# bargraph.net
KiCad netlist of a schematic drawn in EAGLE
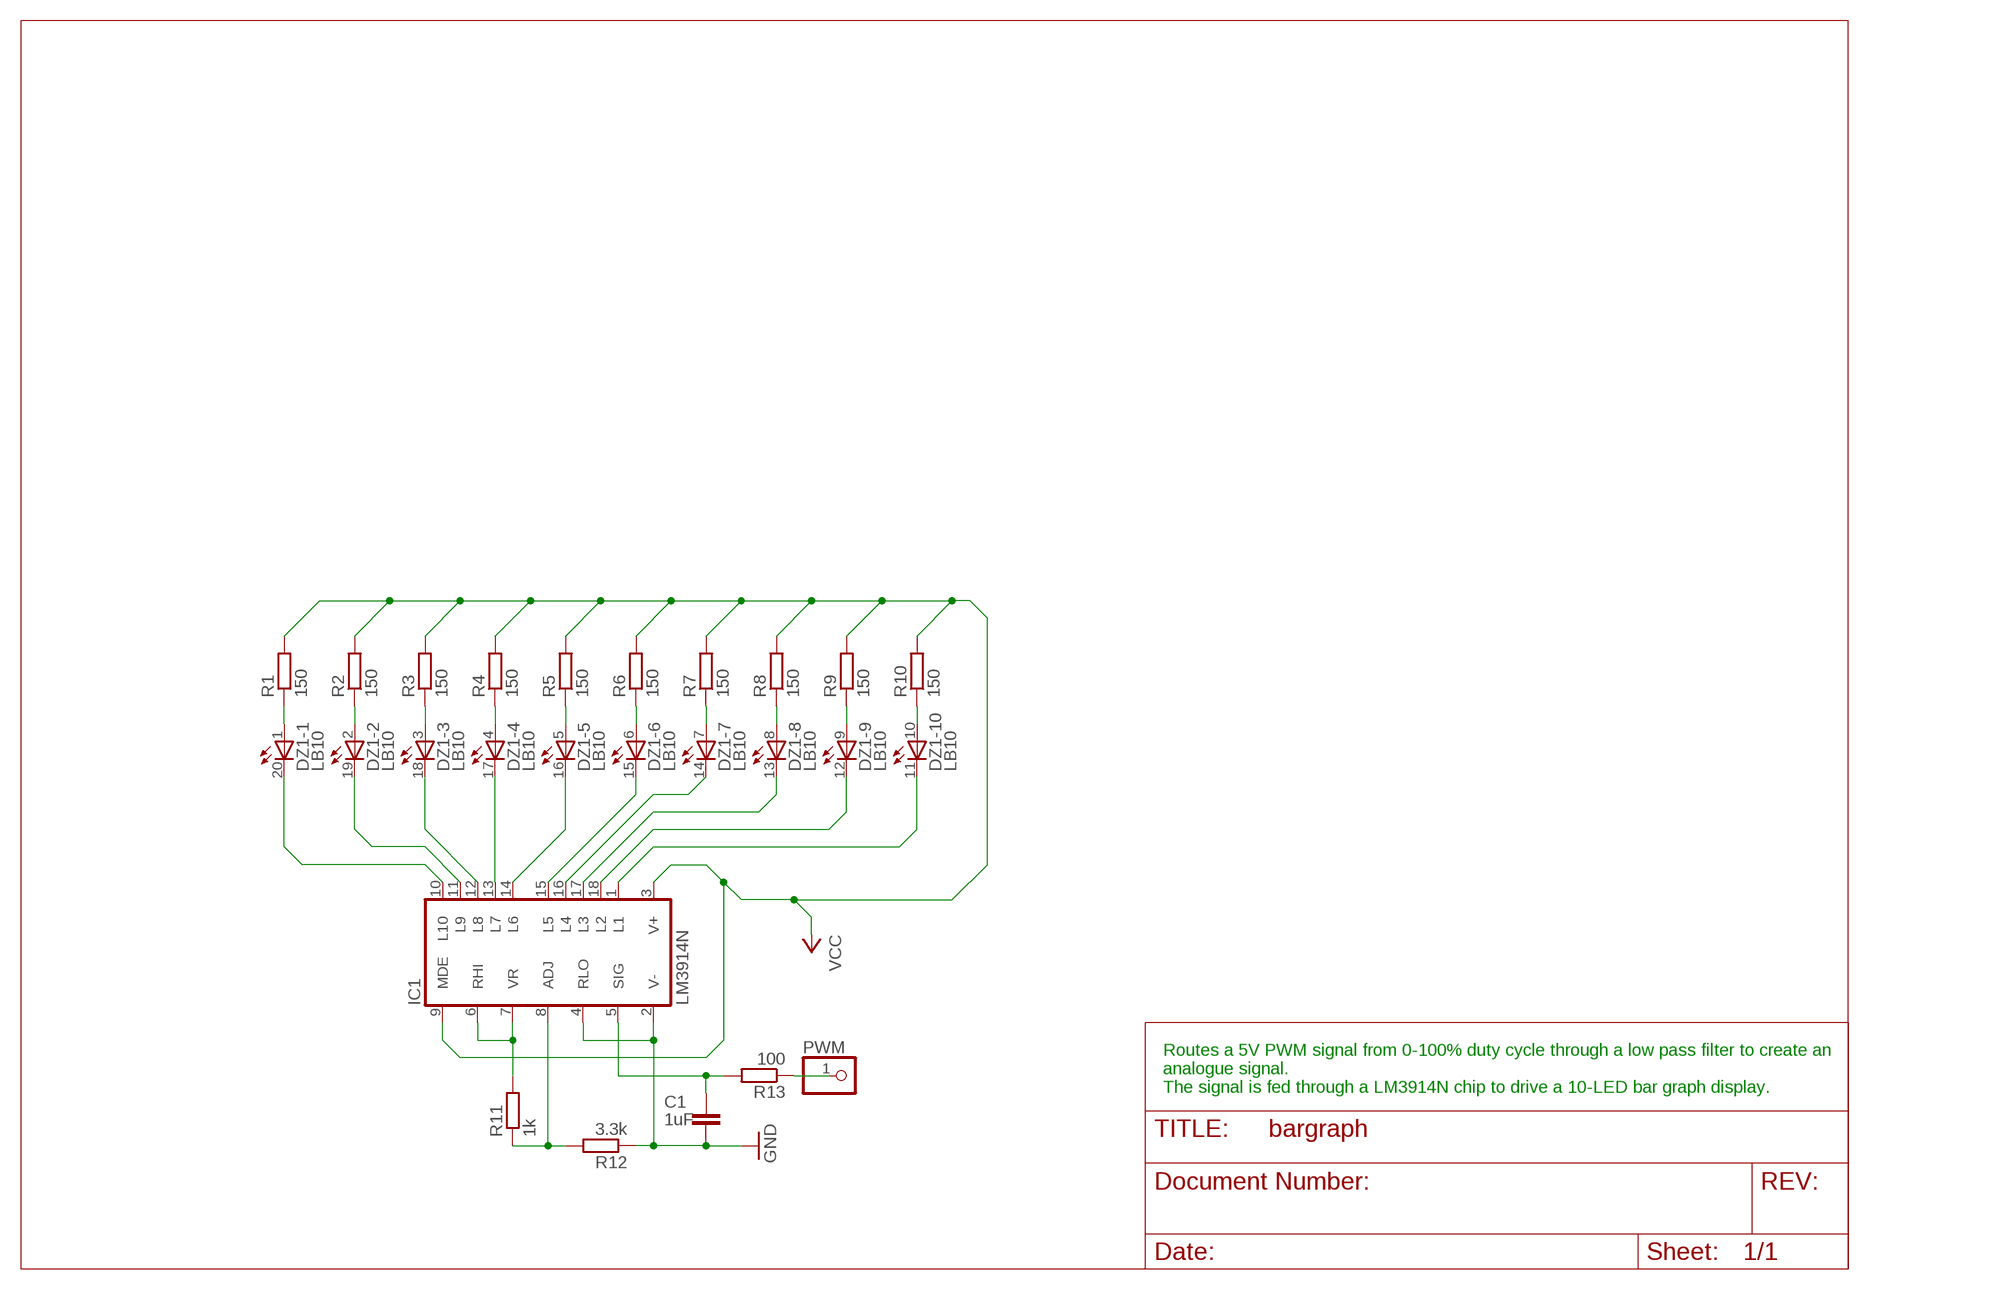
[diagram p0: schematic, sheet 1]

(export (version "E")
  (design (tool "Eeschema 10.0.6"))
  (components
    (comp (ref "C1")
      (value "1uF")
      (footprint "eagle-import:C050-024X044")
      (libsource (lib "eagle-import") (part "C-EU050-024X044"))
    )
    (comp (ref "DZ1")
      (value "LB10")
      (footprint "eagle-import:LB10")
      (libsource (lib "eagle-import") (part "LB10"))
    )
    (comp (ref "IC1")
      (value "LM3914N")
      (footprint "eagle-import:DIL18")
      (libsource (lib "eagle-import") (part "LM3914N"))
    )
    (comp (ref "PWM")
      (value "PINHD-1X1")
      (footprint "eagle-import:1X01")
      (libsource (lib "eagle-import") (part "PINHD-1X1"))
    )
    (comp (ref "R1")
      (value "150")
      (footprint "eagle-import:0207_10")
      (libsource (lib "eagle-import") (part "R-EU_0207/10"))
    )
    (comp (ref "R2")
      (value "150")
      (footprint "eagle-import:0207_10")
      (libsource (lib "eagle-import") (part "R-EU_0207/10"))
    )
    (comp (ref "R3")
      (value "150")
      (footprint "eagle-import:0207_10")
      (libsource (lib "eagle-import") (part "R-EU_0207/10"))
    )
    (comp (ref "R4")
      (value "150")
      (footprint "eagle-import:0207_10")
      (libsource (lib "eagle-import") (part "R-EU_0207/10"))
    )
    (comp (ref "R5")
      (value "150")
      (footprint "eagle-import:0207_10")
      (libsource (lib "eagle-import") (part "R-EU_0207/10"))
    )
    (comp (ref "R6")
      (value "150")
      (footprint "eagle-import:0207_10")
      (libsource (lib "eagle-import") (part "R-EU_0207/10"))
    )
    (comp (ref "R7")
      (value "150")
      (footprint "eagle-import:0207_10")
      (libsource (lib "eagle-import") (part "R-EU_0207/10"))
    )
    (comp (ref "R8")
      (value "150")
      (footprint "eagle-import:0207_10")
      (libsource (lib "eagle-import") (part "R-EU_0207/10"))
    )
    (comp (ref "R9")
      (value "150")
      (footprint "eagle-import:0207_10")
      (libsource (lib "eagle-import") (part "R-EU_0207/10"))
    )
    (comp (ref "R10")
      (value "150")
      (footprint "eagle-import:0207_10")
      (libsource (lib "eagle-import") (part "R-EU_0207/10"))
    )
    (comp (ref "R11")
      (value "1k")
      (footprint "eagle-import:0207_10")
      (libsource (lib "eagle-import") (part "R-EU_0207/10"))
    )
    (comp (ref "R12")
      (value "3.3k")
      (footprint "eagle-import:0207_10")
      (libsource (lib "eagle-import") (part "R-EU_0207/10"))
    )
    (comp (ref "R13")
      (value "100")
      (footprint "eagle-import:0207_10")
      (libsource (lib "eagle-import") (part "R-EU_0207/10"))
    )
  )
  (nets
    (net (code "1") (name "GND") (class "Default")
      (node (ref "C1") (pin "2") (pinfunction "2_2") (pintype "passive"))
      (node (ref "IC1") (pin "2") (pinfunction "V-_2") (pintype "power_in"))
      (node (ref "IC1") (pin "4") (pinfunction "RLO_4") (pintype "input"))
      (node (ref "R12") (pin "1") (pinfunction "1_1") (pintype "passive"))
    )
    (net (code "2") (name "Net-(DZ1A-A)") (class "Default")
      (node (ref "DZ1") (pin "1") (pinfunction "A_1") (pintype "passive"))
      (node (ref "R1") (pin "1") (pinfunction "1_1") (pintype "passive"))
    )
    (net (code "3") (name "Net-(DZ1A-C)") (class "Default")
      (node (ref "DZ1") (pin "20") (pinfunction "C_20") (pintype "passive"))
      (node (ref "IC1") (pin "10") (pinfunction "L10_10") (pintype "output"))
    )
    (net (code "4") (name "Net-(DZ1B-A)") (class "Default")
      (node (ref "DZ1") (pin "10") (pinfunction "A_10") (pintype "passive"))
      (node (ref "R10") (pin "1") (pinfunction "1_1") (pintype "passive"))
    )
    (net (code "5") (name "Net-(DZ1B-C)") (class "Default")
      (node (ref "DZ1") (pin "11") (pinfunction "C_11") (pintype "passive"))
      (node (ref "IC1") (pin "1") (pinfunction "L1_1") (pintype "output"))
    )
    (net (code "6") (name "Net-(DZ1C-A)") (class "Default")
      (node (ref "DZ1") (pin "2") (pinfunction "A_2") (pintype "passive"))
      (node (ref "R2") (pin "1") (pinfunction "1_1") (pintype "passive"))
    )
    (net (code "7") (name "Net-(DZ1C-C)") (class "Default")
      (node (ref "DZ1") (pin "19") (pinfunction "C_19") (pintype "passive"))
      (node (ref "IC1") (pin "11") (pinfunction "L9_11") (pintype "output"))
    )
    (net (code "8") (name "Net-(DZ1D-A)") (class "Default")
      (node (ref "DZ1") (pin "3") (pinfunction "A_3") (pintype "passive"))
      (node (ref "R3") (pin "1") (pinfunction "1_1") (pintype "passive"))
    )
    (net (code "9") (name "Net-(DZ1D-C)") (class "Default")
      (node (ref "DZ1") (pin "18") (pinfunction "C_18") (pintype "passive"))
      (node (ref "IC1") (pin "12") (pinfunction "L8_12") (pintype "output"))
    )
    (net (code "10") (name "Net-(DZ1E-A)") (class "Default")
      (node (ref "DZ1") (pin "4") (pinfunction "A_4") (pintype "passive"))
      (node (ref "R4") (pin "1") (pinfunction "1_1") (pintype "passive"))
    )
    (net (code "11") (name "Net-(DZ1E-C)") (class "Default")
      (node (ref "DZ1") (pin "17") (pinfunction "C_17") (pintype "passive"))
      (node (ref "IC1") (pin "13") (pinfunction "L7_13") (pintype "output"))
    )
    (net (code "12") (name "Net-(DZ1F-A)") (class "Default")
      (node (ref "DZ1") (pin "5") (pinfunction "A_5") (pintype "passive"))
      (node (ref "R5") (pin "1") (pinfunction "1_1") (pintype "passive"))
    )
    (net (code "13") (name "Net-(DZ1F-C)") (class "Default")
      (node (ref "DZ1") (pin "16") (pinfunction "C_16") (pintype "passive"))
      (node (ref "IC1") (pin "14") (pinfunction "L6_14") (pintype "output"))
    )
    (net (code "14") (name "Net-(DZ1G-A)") (class "Default")
      (node (ref "DZ1") (pin "6") (pinfunction "A_6") (pintype "passive"))
      (node (ref "R6") (pin "1") (pinfunction "1_1") (pintype "passive"))
    )
    (net (code "15") (name "Net-(DZ1G-C)") (class "Default")
      (node (ref "DZ1") (pin "15") (pinfunction "C_15") (pintype "passive"))
      (node (ref "IC1") (pin "15") (pinfunction "L5_15") (pintype "output"))
    )
    (net (code "16") (name "Net-(DZ1H-A)") (class "Default")
      (node (ref "DZ1") (pin "7") (pinfunction "A_7") (pintype "passive"))
      (node (ref "R7") (pin "1") (pinfunction "1_1") (pintype "passive"))
    )
    (net (code "17") (name "Net-(DZ1H-C)") (class "Default")
      (node (ref "DZ1") (pin "14") (pinfunction "C_14") (pintype "passive"))
      (node (ref "IC1") (pin "16") (pinfunction "L4_16") (pintype "output"))
    )
    (net (code "18") (name "Net-(DZ1I-A)") (class "Default")
      (node (ref "DZ1") (pin "8") (pinfunction "A_8") (pintype "passive"))
      (node (ref "R8") (pin "1") (pinfunction "1_1") (pintype "passive"))
    )
    (net (code "19") (name "Net-(DZ1I-C)") (class "Default")
      (node (ref "DZ1") (pin "13") (pinfunction "C_13") (pintype "passive"))
      (node (ref "IC1") (pin "17") (pinfunction "L3_17") (pintype "output"))
    )
    (net (code "20") (name "Net-(DZ1J-A)") (class "Default")
      (node (ref "DZ1") (pin "9") (pinfunction "A_9") (pintype "passive"))
      (node (ref "R9") (pin "1") (pinfunction "1_1") (pintype "passive"))
    )
    (net (code "21") (name "Net-(DZ1J-C)") (class "Default")
      (node (ref "DZ1") (pin "12") (pinfunction "C_12") (pintype "passive"))
      (node (ref "IC1") (pin "18") (pinfunction "L2_18") (pintype "output"))
    )
    (net (code "22") (name "Net-(IC1-ADJ)") (class "Default")
      (node (ref "IC1") (pin "8") (pinfunction "ADJ_8") (pintype "input"))
      (node (ref "R11") (pin "1") (pinfunction "1_1") (pintype "passive"))
      (node (ref "R12") (pin "2") (pinfunction "2_2") (pintype "passive"))
    )
    (net (code "23") (name "Net-(IC1-RHI)") (class "Default")
      (node (ref "IC1") (pin "6") (pinfunction "RHI_6") (pintype "input"))
      (node (ref "IC1") (pin "7") (pinfunction "VR_7") (pintype "output"))
      (node (ref "R11") (pin "2") (pinfunction "2_2") (pintype "passive"))
    )
    (net (code "24") (name "Net-(IC1-SIG)") (class "Default")
      (node (ref "C1") (pin "1") (pinfunction "1_1") (pintype "passive"))
      (node (ref "IC1") (pin "5") (pinfunction "SIG_5") (pintype "input"))
      (node (ref "R13") (pin "2") (pinfunction "2_2") (pintype "passive"))
    )
    (net (code "25") (name "Net-(PWM-Pad1)") (class "Default")
      (node (ref "PWM") (pin "1") (pinfunction "1_1") (pintype "passive"))
      (node (ref "R13") (pin "1") (pinfunction "1_1") (pintype "passive"))
    )
    (net (code "26") (name "VCC") (class "Default")
      (node (ref "IC1") (pin "3") (pinfunction "V+_3") (pintype "power_in"))
      (node (ref "IC1") (pin "9") (pinfunction "MDE_9") (pintype "input"))
      (node (ref "R1") (pin "2") (pinfunction "2_2") (pintype "passive"))
      (node (ref "R10") (pin "2") (pinfunction "2_2") (pintype "passive"))
      (node (ref "R2") (pin "2") (pinfunction "2_2") (pintype "passive"))
      (node (ref "R3") (pin "2") (pinfunction "2_2") (pintype "passive"))
      (node (ref "R4") (pin "2") (pinfunction "2_2") (pintype "passive"))
      (node (ref "R5") (pin "2") (pinfunction "2_2") (pintype "passive"))
      (node (ref "R6") (pin "2") (pinfunction "2_2") (pintype "passive"))
      (node (ref "R7") (pin "2") (pinfunction "2_2") (pintype "passive"))
      (node (ref "R8") (pin "2") (pinfunction "2_2") (pintype "passive"))
      (node (ref "R9") (pin "2") (pinfunction "2_2") (pintype "passive"))
    )
  )
)
